# POVDisplayBase.net
KiCad netlist of a schematic drawn in EAGLE
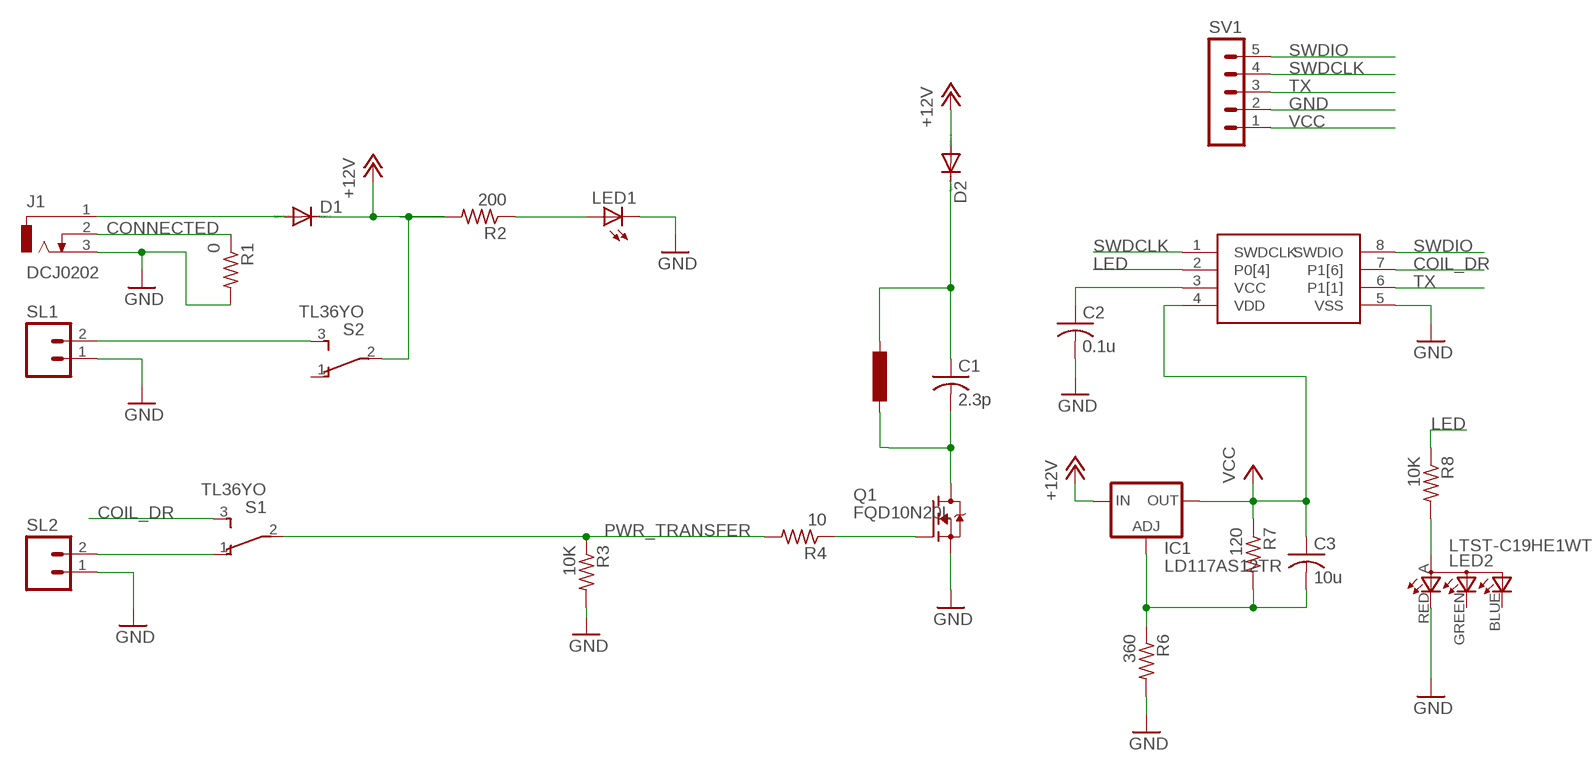
[diagram p0: schematic, sheet 1]

(export (version "E")
  (design (tool "Eeschema 10.0.6"))
  (components
    (comp (ref "C1")
      (value "2.3p")
      (footprint "eagle-import:C1210")
      (libsource (lib "eagle-import") (part "C-USC1210"))
    )
    (comp (ref "C2")
      (value "0.1u")
      (footprint "eagle-import:C0603")
      (libsource (lib "eagle-import") (part "C-USC0603"))
    )
    (comp (ref "C3")
      (value "10u")
      (footprint "eagle-import:C0603")
      (libsource (lib "eagle-import") (part "C-USC0603"))
    )
    (comp (ref "D1")
      (value "DIODE-DO-214AC")
      (footprint "eagle-import:DO-214AC")
      (libsource (lib "eagle-import") (part "DIODE-DO-214AC"))
    )
    (comp (ref "D2")
      (value "DIODE-SMC")
      (footprint "eagle-import:SMC")
      (libsource (lib "eagle-import") (part "DIODE-SMC"))
    )
    (comp (ref "IC1")
      (value "LD117AS12TR")
      (footprint "eagle-import:SOT223")
      (libsource (lib "eagle-import") (part "LD117A?S12TR"))
    )
    (comp (ref "J1")
      (value "DCJ0202")
      (footprint "eagle-import:DCJ0202")
      (libsource (lib "eagle-import") (part "DCJ0202"))
    )
    (comp (ref "LED1")
      (value "LEDCHIPLED_1206")
      (footprint "eagle-import:CHIPLED_1206")
      (libsource (lib "eagle-import") (part "LEDCHIPLED_1206"))
    )
    (comp (ref "LED2")
      (value "LTST-C19HE1WT")
      (footprint "eagle-import:LTST-C19HE1WT")
      (libsource (lib "eagle-import") (part "LTST-C19HE1WT"))
    )
    (comp (ref "Q1")
      (value "FQD10N20L")
      (footprint "eagle-import:TO252")
      (libsource (lib "eagle-import") (part "FQD10N20L"))
    )
    (comp (ref "R1")
      (value "0")
      (footprint "eagle-import:R0603")
      (libsource (lib "eagle-import") (part "R-US_R0603"))
    )
    (comp (ref "R2")
      (value "200")
      (footprint "eagle-import:R0603")
      (libsource (lib "eagle-import") (part "R-US_R0603"))
    )
    (comp (ref "R3")
      (value "10K")
      (footprint "eagle-import:R0603")
      (libsource (lib "eagle-import") (part "R-US_R0603"))
    )
    (comp (ref "R4")
      (value "10")
      (footprint "eagle-import:R0603")
      (libsource (lib "eagle-import") (part "R-US_R0603"))
    )
    (comp (ref "R6")
      (value "360")
      (footprint "eagle-import:R0603")
      (libsource (lib "eagle-import") (part "R-US_R0603"))
    )
    (comp (ref "R7")
      (value "120")
      (footprint "eagle-import:R0603")
      (libsource (lib "eagle-import") (part "R-US_R0603"))
    )
    (comp (ref "R8")
      (value "10K")
      (footprint "eagle-import:R0603")
      (libsource (lib "eagle-import") (part "R-US_R0603"))
    )
    (comp (ref "S1")
      (value "TL36YO")
      (footprint "eagle-import:TL3XYO")
      (libsource (lib "eagle-import") (part "TL36YO"))
    )
    (comp (ref "S2")
      (value "TL36YO")
      (footprint "eagle-import:TL3XYO")
      (libsource (lib "eagle-import") (part "TL36YO"))
    )
    (comp (ref "SL1")
      (value "M02")
      (footprint "eagle-import:02P")
      (libsource (lib "eagle-import") (part "M02"))
    )
    (comp (ref "SL2")
      (value "M02")
      (footprint "eagle-import:02P")
      (libsource (lib "eagle-import") (part "M02"))
    )
    (comp (ref "SV1")
      (value "MA05-1")
      (footprint "eagle-import:MA05-1")
      (libsource (lib "eagle-import") (part "MA05-1"))
    )
    (comp (ref "U1")
      (value "CY8C4013SXI-400")
      (footprint "eagle-import:SOIC08")
      (libsource (lib "eagle-import") (part "CY8C4013SXI-400"))
    )
  )
  (nets
    (net (code "1") (name "+12V") (class "Default")
      (node (ref "D1") (pin "C") (pinfunction "C_C") (pintype "passive"))
      (node (ref "D2") (pin "A") (pinfunction "A_A") (pintype "passive"))
      (node (ref "IC1") (pin "3") (pinfunction "IN_3") (pintype "input"))
      (node (ref "R2") (pin "2") (pinfunction "2_2") (pintype "passive"))
      (node (ref "S2") (pin "2") (pinfunction "P_2") (pintype "passive"))
    )
    (net (code "2") (name "/COIL_DR") (class "Default")
      (node (ref "S1") (pin "3") (pinfunction "S_3") (pintype "passive"))
      (node (ref "U1") (pin "7") (pinfunction "P1[6]_7") (pintype "bidirectional"))
    )
    (net (code "3") (name "/CONNECTED") (class "Default")
      (node (ref "J1") (pin "2") (pinfunction "2_2") (pintype "passive"))
      (node (ref "R1") (pin "1") (pinfunction "1_1") (pintype "passive"))
    )
    (net (code "4") (name "/LED") (class "Default")
      (node (ref "R8") (pin "1") (pinfunction "1_1") (pintype "passive"))
      (node (ref "U1") (pin "2") (pinfunction "P0[4]_2") (pintype "bidirectional"))
    )
    (net (code "5") (name "/PWR_TRANSFER") (class "Default")
      (node (ref "R3") (pin "1") (pinfunction "1_1") (pintype "passive"))
      (node (ref "R4") (pin "2") (pinfunction "2_2") (pintype "passive"))
      (node (ref "S1") (pin "2") (pinfunction "P_2") (pintype "passive"))
    )
    (net (code "6") (name "/SWDCLK") (class "Default")
      (node (ref "SV1") (pin "4") (pinfunction "4_4") (pintype "passive"))
      (node (ref "U1") (pin "1") (pinfunction "SWDCLK_1") (pintype "bidirectional"))
    )
    (net (code "7") (name "/SWDIO") (class "Default")
      (node (ref "SV1") (pin "5") (pinfunction "5_5") (pintype "passive"))
      (node (ref "U1") (pin "8") (pinfunction "SWDIO_8") (pintype "bidirectional"))
    )
    (net (code "8") (name "/TX") (class "Default")
      (node (ref "SV1") (pin "3") (pinfunction "3_3") (pintype "passive"))
      (node (ref "U1") (pin "6") (pinfunction "P1[1]_6") (pintype "bidirectional"))
    )
    (net (code "9") (name "GND") (class "Default")
      (node (ref "C2") (pin "2") (pinfunction "2_2") (pintype "passive"))
      (node (ref "J1") (pin "3") (pinfunction "3_3") (pintype "passive"))
      (node (ref "LED1") (pin "C") (pinfunction "C_C") (pintype "passive"))
      (node (ref "LED2") (pin "RED") (pinfunction "CRED_RED") (pintype "passive"))
      (node (ref "Q1") (pin "2") (pinfunction "S_2") (pintype "passive"))
      (node (ref "R1") (pin "2") (pinfunction "2_2") (pintype "passive"))
      (node (ref "R3") (pin "2") (pinfunction "2_2") (pintype "passive"))
      (node (ref "R6") (pin "2") (pinfunction "2_2") (pintype "passive"))
      (node (ref "SL1") (pin "1") (pinfunction "1_1") (pintype "passive"))
      (node (ref "SL2") (pin "1") (pinfunction "1_1") (pintype "passive"))
      (node (ref "SV1") (pin "2") (pinfunction "2_2") (pintype "passive"))
      (node (ref "U1") (pin "5") (pinfunction "VSS_5") (pintype "bidirectional"))
    )
    (net (code "10") (name "Net-(C1-Pad1)") (class "Default")
      (node (ref "C1") (pin "1") (pinfunction "1_1") (pintype "passive"))
      (node (ref "D2") (pin "C") (pinfunction "C_C") (pintype "passive"))
    )
    (net (code "11") (name "Net-(D1-PadA)") (class "Default")
      (node (ref "D1") (pin "A") (pinfunction "A_A") (pintype "passive"))
      (node (ref "J1") (pin "1") (pinfunction "1_1") (pintype "passive"))
    )
    (net (code "12") (name "Net-(IC1-ADJ)") (class "Default")
      (node (ref "C3") (pin "2") (pinfunction "2_2") (pintype "passive"))
      (node (ref "IC1") (pin "1") (pinfunction "ADJ_1") (pintype "input"))
      (node (ref "R6") (pin "1") (pinfunction "1_1") (pintype "passive"))
      (node (ref "R7") (pin "2") (pinfunction "2_2") (pintype "passive"))
    )
    (net (code "13") (name "Net-(LED1-PadA)") (class "Default")
      (node (ref "LED1") (pin "A") (pinfunction "A_A") (pintype "passive"))
      (node (ref "R2") (pin "1") (pinfunction "1_1") (pintype "passive"))
    )
    (net (code "14") (name "Net-(LED2-PadA)") (class "Default")
      (node (ref "LED2") (pin "A") (pinfunction "A_A") (pintype "passive"))
      (node (ref "R8") (pin "2") (pinfunction "2_2") (pintype "passive"))
    )
    (net (code "15") (name "Net-(Q1-D)") (class "Default")
      (node (ref "C1") (pin "2") (pinfunction "2_2") (pintype "passive"))
      (node (ref "Q1") (pin "3") (pinfunction "D_3") (pintype "passive"))
    )
    (net (code "16") (name "Net-(Q1-G)") (class "Default")
      (node (ref "Q1") (pin "1") (pinfunction "G_1") (pintype "passive"))
      (node (ref "R4") (pin "1") (pinfunction "1_1") (pintype "passive"))
    )
    (net (code "17") (name "Net-(S1-O)") (class "Default")
      (node (ref "S1") (pin "1") (pinfunction "O_1") (pintype "passive"))
      (node (ref "SL2") (pin "2") (pinfunction "2_2") (pintype "passive"))
    )
    (net (code "18") (name "Net-(S2-S)") (class "Default")
      (node (ref "S2") (pin "3") (pinfunction "S_3") (pintype "passive"))
      (node (ref "SL1") (pin "2") (pinfunction "2_2") (pintype "passive"))
    )
    (net (code "19") (name "Net-(U1-VCC)") (class "Default")
      (node (ref "C2") (pin "1") (pinfunction "1_1") (pintype "passive"))
      (node (ref "U1") (pin "3") (pinfunction "VCC_3") (pintype "bidirectional"))
    )
    (net (code "20") (name "VCC") (class "Default")
      (node (ref "C3") (pin "1") (pinfunction "1_1") (pintype "passive"))
      (node (ref "IC1") (pin "4") (pinfunction "OUT_4") (pintype "passive"))
      (node (ref "R7") (pin "1") (pinfunction "1_1") (pintype "passive"))
      (node (ref "SV1") (pin "1") (pinfunction "1_1") (pintype "passive"))
      (node (ref "U1") (pin "4") (pinfunction "VDD_4") (pintype "bidirectional"))
    )
    (net (code "21") (name "unconnected-(LED2-CBLUE-PadBLUE)") (class "Default")
      (node (ref "LED2") (pin "BLUE") (pinfunction "CBLUE_BLUE") (pintype "passive"))
    )
    (net (code "22") (name "unconnected-(LED2-CGREEN-PadGREEN)") (class "Default")
      (node (ref "LED2") (pin "GREEN") (pinfunction "CGREEN_GREEN") (pintype "passive"))
    )
    (net (code "23") (name "unconnected-(S2-O-Pad1)") (class "Default")
      (node (ref "S2") (pin "1") (pinfunction "O_1") (pintype "passive"))
    )
  )
)
